# Sheet1.net
KiCad netlist of a schematic drawn in Altium Designer
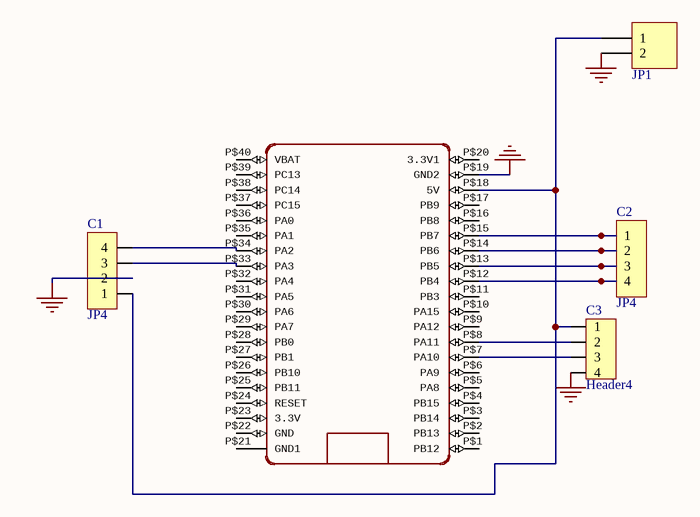
[diagram p0: Sheet1.SchDoc]

(export (version "E")
  (design (tool "Eeschema 10.0.6"))
  (components
    (comp (ref "C1")
      (value "JP4")
      (footprint "JP4-C1T")
      (description "WR-PHD 2.54 mm Angled Socket Header")
      (fields
        (field (name "MANUFACTURER") "Würth Elektronik eiSos GmbH")
        (field (name "PARTNO") "613004143121")
        (field (name "CREATED BY") "Karrer Zheng")
      )
      (libsource (lib "LIBRARYALT") (part "JP4"))
    )
    (comp (ref "C2")
      (value "JP4")
      (footprint "JP4-C1T")
      (description "WR-PHD 2.54 mm Angled Socket Header")
      (fields
        (field (name "MANUFACTURER") "Würth Elektronik eiSos GmbH")
        (field (name "PARTNO") "613004143121")
        (field (name "CREATED BY") "Karrer Zheng")
      )
      (libsource (lib "") (part "JP4_1"))
    )
    (comp (ref "C3")
      (value "Header4")
      (footprint "Header4")
      (description "Header IDC, 4 x 1 Pin Vertical 2.54mm Pitch (Non-Boxed, Male)")
      (fields
        (field (name "MANUFACTURER") "Würth Elektronik eiSos GmbH")
        (field (name "PARTNO") "613002143121")
        (field (name "CREATED BY") "Karrer Zheng")
      )
      (libsource (lib "LIBRARYALT") (part "Header4"))
    )
    (comp (ref "JP1")
      (value "Header 2_1")
      (footprint "HED2")
      (description "Header, 2-Pin")
      (fields (field (name "MANUFACTURER") "Generic Components"))
      (libsource (lib "echipkool-com-library") (part "Header 2_1"))
    )
    (comp (ref "U")
      (value "BLUE_PILL")
      (footprint "BLUE_PILL")
      (libsource (lib "BluePill") (part "BLUE_PILL"))
    )
  )
  (nets
    (net (code "1") (name "GND") (class "Default")
      (node (ref "C1") (pin "2") (pinfunction "2_2") (pintype "passive"))
      (node (ref "C3") (pin "4") (pinfunction "4_4") (pintype "passive"))
      (node (ref "JP1") (pin "2") (pinfunction "2_2") (pintype "passive"))
      (node (ref "U") (pin "P$19") (pinfunction "GND2_P$19") (pintype "bidirectional"))
    )
    (net (code "2") (name "Net-(U-5V)") (class "Default")
      (node (ref "C1") (pin "1") (pinfunction "1_1") (pintype "passive"))
      (node (ref "C3") (pin "1") (pinfunction "1_1") (pintype "passive"))
      (node (ref "JP1") (pin "1") (pinfunction "1_1") (pintype "passive"))
      (node (ref "U") (pin "P$18") (pinfunction "5V_P$18") (pintype "bidirectional"))
    )
    (net (code "3") (name "Net-(U-PA2)") (class "Default")
      (node (ref "C1") (pin "4") (pinfunction "4_4") (pintype "passive"))
      (node (ref "U") (pin "P$34") (pinfunction "PA2_P$34") (pintype "bidirectional"))
    )
    (net (code "4") (name "Net-(U-PA3)") (class "Default")
      (node (ref "C1") (pin "3") (pinfunction "3_3") (pintype "passive"))
      (node (ref "U") (pin "P$33") (pinfunction "PA3_P$33") (pintype "bidirectional"))
    )
    (net (code "5") (name "Net-(U-PA10)") (class "Default")
      (node (ref "C3") (pin "3") (pinfunction "3_3") (pintype "passive"))
      (node (ref "U") (pin "P$7") (pinfunction "PA10_P$7") (pintype "bidirectional"))
    )
    (net (code "6") (name "Net-(U-PA11)") (class "Default")
      (node (ref "C3") (pin "2") (pinfunction "2_2") (pintype "passive"))
      (node (ref "U") (pin "P$8") (pinfunction "PA11_P$8") (pintype "bidirectional"))
    )
    (net (code "7") (name "Net-(U-PB4)") (class "Default")
      (node (ref "C2") (pin "4") (pinfunction "4_4") (pintype "passive"))
      (node (ref "U") (pin "P$12") (pinfunction "PB4_P$12") (pintype "bidirectional"))
    )
    (net (code "8") (name "Net-(U-PB5)") (class "Default")
      (node (ref "C2") (pin "3") (pinfunction "3_3") (pintype "passive"))
      (node (ref "U") (pin "P$13") (pinfunction "PB5_P$13") (pintype "bidirectional"))
    )
    (net (code "9") (name "Net-(U-PB6)") (class "Default")
      (node (ref "C2") (pin "2") (pinfunction "2_2") (pintype "passive"))
      (node (ref "U") (pin "P$14") (pinfunction "PB6_P$14") (pintype "bidirectional"))
    )
    (net (code "10") (name "Net-(U-PB7)") (class "Default")
      (node (ref "C2") (pin "1") (pinfunction "1_1") (pintype "passive"))
      (node (ref "U") (pin "P$15") (pinfunction "PB7_P$15") (pintype "bidirectional"))
    )
    (net (code "11") (name "unconnected-(U-3.3V-PadP$23)") (class "Default")
      (node (ref "U") (pin "P$23") (pinfunction "3.3V_P$23") (pintype "bidirectional"))
    )
    (net (code "12") (name "unconnected-(U-3.3V1-PadP$20)") (class "Default")
      (node (ref "U") (pin "P$20") (pinfunction "3.3V1_P$20") (pintype "bidirectional"))
    )
    (net (code "13") (name "unconnected-(U-GND-PadP$22)") (class "Default")
      (node (ref "U") (pin "P$22") (pinfunction "GND_P$22") (pintype "bidirectional"))
    )
    (net (code "14") (name "unconnected-(U-GND1-PadP$21)") (class "Default")
      (node (ref "U") (pin "P$21") (pinfunction "GND1_P$21") (pintype "power_in"))
    )
    (net (code "15") (name "unconnected-(U-PA0-PadP$36)") (class "Default")
      (node (ref "U") (pin "P$36") (pinfunction "PA0_P$36") (pintype "bidirectional"))
    )
    (net (code "16") (name "unconnected-(U-PA1-PadP$35)") (class "Default")
      (node (ref "U") (pin "P$35") (pinfunction "PA1_P$35") (pintype "bidirectional"))
    )
    (net (code "17") (name "unconnected-(U-PA4-PadP$32)") (class "Default")
      (node (ref "U") (pin "P$32") (pinfunction "PA4_P$32") (pintype "bidirectional"))
    )
    (net (code "18") (name "unconnected-(U-PA5-PadP$31)") (class "Default")
      (node (ref "U") (pin "P$31") (pinfunction "PA5_P$31") (pintype "bidirectional"))
    )
    (net (code "19") (name "unconnected-(U-PA6-PadP$30)") (class "Default")
      (node (ref "U") (pin "P$30") (pinfunction "PA6_P$30") (pintype "bidirectional"))
    )
    (net (code "20") (name "unconnected-(U-PA7-PadP$29)") (class "Default")
      (node (ref "U") (pin "P$29") (pinfunction "PA7_P$29") (pintype "bidirectional"))
    )
    (net (code "21") (name "unconnected-(U-PA8-PadP$5)") (class "Default")
      (node (ref "U") (pin "P$5") (pinfunction "PA8_P$5") (pintype "bidirectional"))
    )
    (net (code "22") (name "unconnected-(U-PA9-PadP$6)") (class "Default")
      (node (ref "U") (pin "P$6") (pinfunction "PA9_P$6") (pintype "bidirectional"))
    )
    (net (code "23") (name "unconnected-(U-PA12-PadP$9)") (class "Default")
      (node (ref "U") (pin "P$9") (pinfunction "PA12_P$9") (pintype "bidirectional"))
    )
    (net (code "24") (name "unconnected-(U-PA15-PadP$10)") (class "Default")
      (node (ref "U") (pin "P$10") (pinfunction "PA15_P$10") (pintype "bidirectional"))
    )
    (net (code "25") (name "unconnected-(U-PB0-PadP$28)") (class "Default")
      (node (ref "U") (pin "P$28") (pinfunction "PB0_P$28") (pintype "bidirectional"))
    )
    (net (code "26") (name "unconnected-(U-PB1-PadP$27)") (class "Default")
      (node (ref "U") (pin "P$27") (pinfunction "PB1_P$27") (pintype "bidirectional"))
    )
    (net (code "27") (name "unconnected-(U-PB3-PadP$11)") (class "Default")
      (node (ref "U") (pin "P$11") (pinfunction "PB3_P$11") (pintype "bidirectional"))
    )
    (net (code "28") (name "unconnected-(U-PB8-PadP$16)") (class "Default")
      (node (ref "U") (pin "P$16") (pinfunction "PB8_P$16") (pintype "bidirectional"))
    )
    (net (code "29") (name "unconnected-(U-PB9-PadP$17)") (class "Default")
      (node (ref "U") (pin "P$17") (pinfunction "PB9_P$17") (pintype "bidirectional"))
    )
    (net (code "30") (name "unconnected-(U-PB10-PadP$26)") (class "Default")
      (node (ref "U") (pin "P$26") (pinfunction "PB10_P$26") (pintype "bidirectional"))
    )
    (net (code "31") (name "unconnected-(U-PB11-PadP$25)") (class "Default")
      (node (ref "U") (pin "P$25") (pinfunction "PB11_P$25") (pintype "bidirectional"))
    )
    (net (code "32") (name "unconnected-(U-PB12-PadP$1)") (class "Default")
      (node (ref "U") (pin "P$1") (pinfunction "PB12_P$1") (pintype "bidirectional"))
    )
    (net (code "33") (name "unconnected-(U-PB13-PadP$2)") (class "Default")
      (node (ref "U") (pin "P$2") (pinfunction "PB13_P$2") (pintype "bidirectional"))
    )
    (net (code "34") (name "unconnected-(U-PB14-PadP$3)") (class "Default")
      (node (ref "U") (pin "P$3") (pinfunction "PB14_P$3") (pintype "bidirectional"))
    )
    (net (code "35") (name "unconnected-(U-PB15-PadP$4)") (class "Default")
      (node (ref "U") (pin "P$4") (pinfunction "PB15_P$4") (pintype "bidirectional"))
    )
    (net (code "36") (name "unconnected-(U-PC13-PadP$39)") (class "Default")
      (node (ref "U") (pin "P$39") (pinfunction "PC13_P$39") (pintype "bidirectional"))
    )
    (net (code "37") (name "unconnected-(U-PC14-PadP$38)") (class "Default")
      (node (ref "U") (pin "P$38") (pinfunction "PC14_P$38") (pintype "bidirectional"))
    )
    (net (code "38") (name "unconnected-(U-PC15-PadP$37)") (class "Default")
      (node (ref "U") (pin "P$37") (pinfunction "PC15_P$37") (pintype "bidirectional"))
    )
    (net (code "39") (name "unconnected-(U-RESET-PadP$24)") (class "Default")
      (node (ref "U") (pin "P$24") (pinfunction "RESET_P$24") (pintype "bidirectional"))
    )
    (net (code "40") (name "unconnected-(U-VBAT-PadP$40)") (class "Default")
      (node (ref "U") (pin "P$40") (pinfunction "VBAT_P$40") (pintype "bidirectional"))
    )
  )
)
